# Output_Schematic.net
KiCad netlist of a schematic drawn in Altium Designer
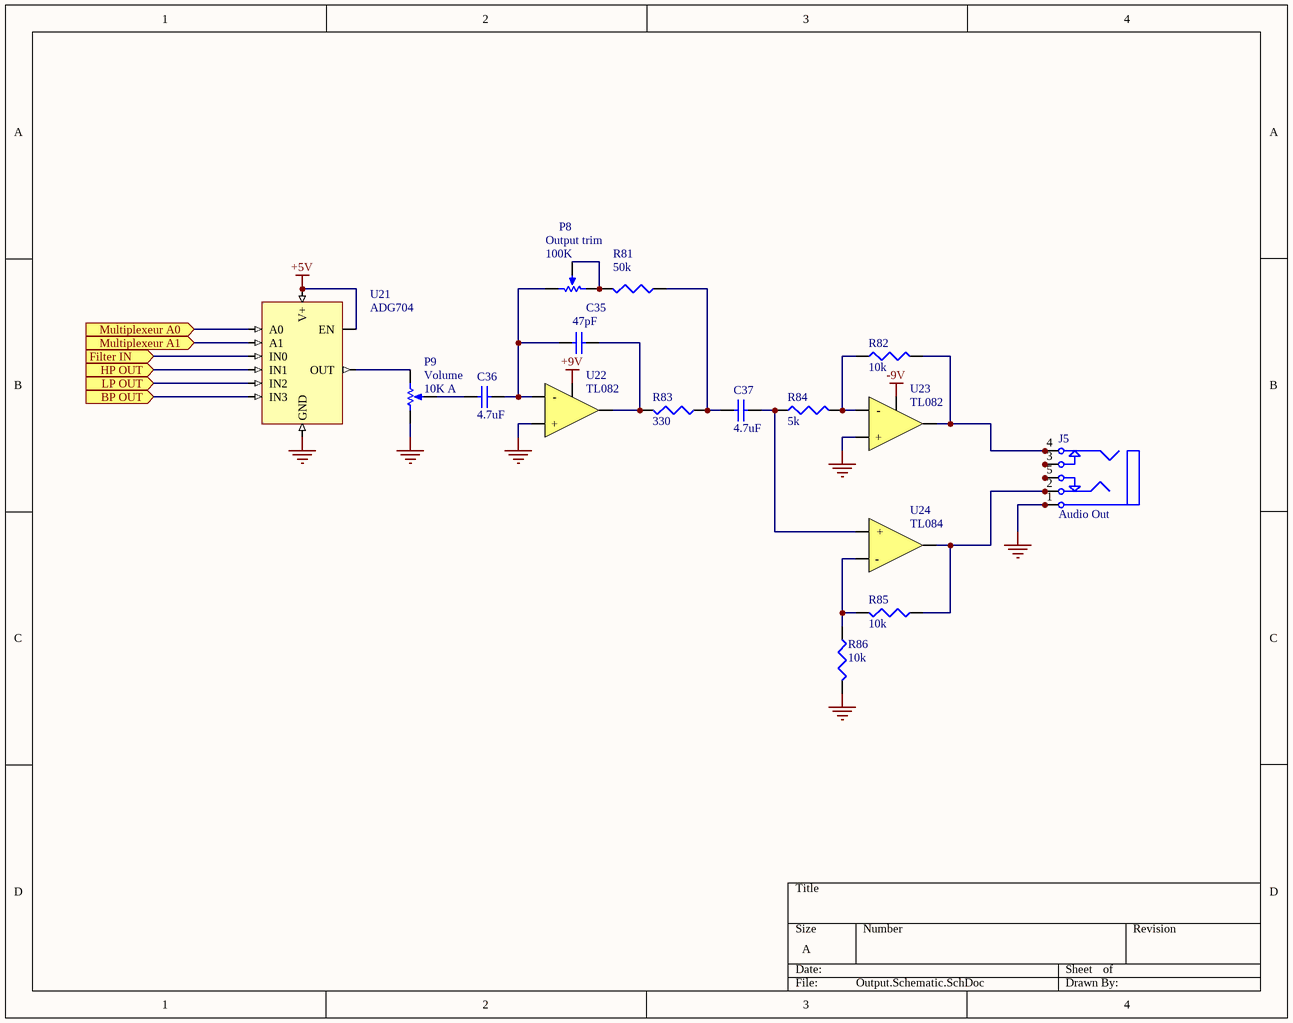
[diagram p0: Output.Schematic.SchDoc]

(export (version "E")
  (design (tool "Eeschema 10.0.6"))
  (components
    (comp (ref "C35")
      (value "47pF")
      (footprint "CAPC1608N")
      (description "Capacitor (Semiconductor SIM Model)")
      (fields (field (name "PUBLISHER") "Altium Limited"))
      (libsource (lib "Miscellaneous Devices") (part "Cap Semi"))
    )
    (comp (ref "C36")
      (value "4.7uF")
      (footprint "CAPC1608N")
      (description "Capacitor (Semiconductor SIM Model)")
      (fields (field (name "PUBLISHER") "Altium Limited"))
      (libsource (lib "Miscellaneous Devices") (part "Cap Semi"))
    )
    (comp (ref "C37")
      (value "4.7uF")
      (footprint "CAPC1608N")
      (description "Capacitor (Semiconductor SIM Model)")
      (fields (field (name "PUBLISHER") "Altium Limited"))
      (libsource (lib "Miscellaneous Devices") (part "Cap Semi"))
    )
    (comp (ref "J5")
      (value "Audio Out")
      (footprint "ST-3150-5N")
      (description "3-Conductor Jack with 2 break contacts (normals) and 2 auxiliary make contacts")
      (fields (field (name "PUBLISHER") "Altium Limited"))
      (libsource (lib "Miscellaneous Connectors") (part "Phonejack Stereo SW"))
    )
    (comp (ref "P8")
      (value "Output trim")
      (footprint "BOURNS Trim pot")
      (description "Potentiometer")
      (fields (field (name "ALTIUM_VALUE") "100K") (field (name "PUBLISHER") "Altium Limited"))
      (libsource (lib "Miscellaneous Devices") (part "RPot"))
    )
    (comp (ref "P9")
      (value "Volume")
      (footprint "ALPS Potentiometer")
      (description "Potentiometer")
      (fields (field (name "ALTIUM_VALUE") "10K A") (field (name "PUBLISHER") "Altium Limited"))
      (libsource (lib "Miscellaneous Devices") (part "RPot"))
    )
    (comp (ref "R81")
      (value "50k")
      (footprint "CAPC1608N")
      (description "Resistor")
      (fields (field (name "PUBLISHER") "Altium Limited"))
      (libsource (lib "Miscellaneous Devices") (part "Res3"))
    )
    (comp (ref "R82")
      (value "10k")
      (footprint "CAPC1608N")
      (description "Resistor")
      (fields (field (name "PUBLISHER") "Altium Limited"))
      (libsource (lib "Miscellaneous Devices") (part "Res3"))
    )
    (comp (ref "R83")
      (value "330")
      (footprint "CAPC1608N")
      (description "Resistor")
      (fields (field (name "PUBLISHER") "Altium Limited"))
      (libsource (lib "Miscellaneous Devices") (part "Res3"))
    )
    (comp (ref "R84")
      (value "5k")
      (footprint "CAPC1608N")
      (description "Resistor")
      (fields (field (name "PUBLISHER") "Altium Limited"))
      (libsource (lib "Miscellaneous Devices") (part "Res3"))
    )
    (comp (ref "R85")
      (value "10k")
      (footprint "J1-0603")
      (description "Resistor")
      (fields (field (name "PUBLISHER") "Altium Limited"))
      (libsource (lib "Miscellaneous Devices") (part "Res3"))
    )
    (comp (ref "R86")
      (value "10k")
      (footprint "RESC6332")
      (description "Resistor")
      (fields (field (name "PUBLISHER") "Altium Limited"))
      (libsource (lib "Miscellaneous Devices") (part "Res3"))
    )
    (comp (ref "U21")
      (value "ADG704")
      (footprint "ADG704")
      (libsource (lib "SynthyTwo.Components") (part "ADG704"))
    )
    (comp (ref "U22")
      (value "TL082")
      (footprint "TL084_3PADS+ALIM")
      (libsource (lib "SynthyTwo.Components") (part "TL082"))
    )
    (comp (ref "U23")
      (value "TL082")
      (footprint "TL084_3PADS+ALIM")
      (libsource (lib "SynthyTwo.Components") (part "TL082"))
    )
    (comp (ref "U24")
      (value "TL084")
      (footprint "TL084_3PADS")
      (libsource (lib "SynthyTwo.Components") (part "TL084"))
    )
  )
  (nets
    (net (code "1") (name "+5V") (class "Default")
      (node (ref "U21") (pin "5") (pinfunction "EN_5") (pintype "passive"))
      (node (ref "U21") (pin "6") (pinfunction "V+_6") (pintype "input"))
    )
    (net (code "2") (name "+9V") (class "Default")
      (node (ref "U22") (pin "4") (pinfunction "VCC+_4") (pintype "passive"))
    )
    (net (code "3") (name "-9V") (class "Default")
      (node (ref "U23") (pin "4") (pinfunction "VCC+_4") (pintype "passive"))
    )
    (net (code "4") (name "/BP OUT") (class "Default")
      (node (ref "U21") (pin "7") (pinfunction "IN3_7") (pintype "input"))
    )
    (net (code "5") (name "/Filter IN") (class "Default")
      (node (ref "U21") (pin "2") (pinfunction "IN0_2") (pintype "input"))
    )
    (net (code "6") (name "/HP OUT") (class "Default")
      (node (ref "U21") (pin "9") (pinfunction "IN1_9") (pintype "input"))
    )
    (net (code "7") (name "/LP OUT") (class "Default")
      (node (ref "U21") (pin "4") (pinfunction "IN2_4") (pintype "input"))
    )
    (net (code "8") (name "/Multiplexeur A0") (class "Default")
      (node (ref "U21") (pin "1") (pinfunction "A0_1") (pintype "input"))
    )
    (net (code "9") (name "/Multiplexeur A1") (class "Default")
      (node (ref "U21") (pin "10") (pinfunction "A1_10") (pintype "input"))
    )
    (net (code "10") (name "GND") (class "Default")
      (node (ref "J5") (pin "1") (pinfunction "1_1") (pintype "passive"))
      (node (ref "J5") (pin "1A") (pinfunction "1A_1A") (pintype "passive"))
      (node (ref "J5") (pin "1B") (pinfunction "1B_1B") (pintype "passive"))
      (node (ref "P9") (pin "1") (pinfunction "TOP_1") (pintype "passive"))
      (node (ref "R86") (pin "2") (pinfunction "2_2") (pintype "passive"))
      (node (ref "U21") (pin "3") (pinfunction "GND_3") (pintype "input"))
      (node (ref "U22") (pin "3") (pinfunction "+_3") (pintype "passive"))
      (node (ref "U23") (pin "3") (pinfunction "+_3") (pintype "passive"))
    )
    (net (code "11") (name "Net-(C37-Pad1)") (class "Default")
      (node (ref "C37") (pin "1") (pinfunction "1_1") (pintype "passive"))
      (node (ref "R81") (pin "1") (pinfunction "1_1") (pintype "passive"))
      (node (ref "R83") (pin "1") (pinfunction "1_1") (pintype "passive"))
    )
    (net (code "12") (name "Net-(J5-Pad3)") (class "Default")
      (node (ref "J5") (pin "3") (pinfunction "3_3") (pintype "passive"))
      (node (ref "J5") (pin "3A") (pinfunction "3A_3A") (pintype "passive"))
      (node (ref "J5") (pin "3B") (pinfunction "3B_3B") (pintype "passive"))
    )
    (net (code "13") (name "Net-(J5-Pad5)") (class "Default")
      (node (ref "J5") (pin "5") (pinfunction "5_5") (pintype "passive"))
      (node (ref "J5") (pin "5A") (pinfunction "5A_5A") (pintype "passive"))
      (node (ref "J5") (pin "5B") (pinfunction "5B_5B") (pintype "passive"))
    )
    (net (code "14") (name "Net-(P8-BOT)") (class "Default")
      (node (ref "P8") (pin "2") (pinfunction "BOT_2") (pintype "passive"))
      (node (ref "P8") (pin "3") (pinfunction "TAP_3") (pintype "passive"))
      (node (ref "R81") (pin "2") (pinfunction "2_2") (pintype "passive"))
    )
    (net (code "15") (name "Net-(P8-TOP)") (class "Default")
      (node (ref "C35") (pin "1") (pinfunction "1_1") (pintype "passive"))
      (node (ref "C36") (pin "2") (pinfunction "2_2") (pintype "passive"))
      (node (ref "P8") (pin "1") (pinfunction "TOP_1") (pintype "passive"))
      (node (ref "U22") (pin "2") (pinfunction "-_2") (pintype "passive"))
    )
    (net (code "16") (name "Net-(P9-BOT)") (class "Default")
      (node (ref "P9") (pin "2") (pinfunction "BOT_2") (pintype "passive"))
      (node (ref "U21") (pin "8") (pinfunction "OUT_8") (pintype "output"))
    )
    (net (code "17") (name "Net-(P9-TAP)") (class "Default")
      (node (ref "C36") (pin "1") (pinfunction "1_1") (pintype "passive"))
      (node (ref "P9") (pin "3") (pinfunction "TAP_3") (pintype "passive"))
    )
    (net (code "18") (name "Net-(U22-OUT)") (class "Default")
      (node (ref "C35") (pin "2") (pinfunction "2_2") (pintype "passive"))
      (node (ref "R83") (pin "2") (pinfunction "2_2") (pintype "passive"))
      (node (ref "U22") (pin "1") (pinfunction "OUT_1") (pintype "passive"))
    )
    (net (code "19") (name "Net-(U23--)") (class "Default")
      (node (ref "R82") (pin "1") (pinfunction "1_1") (pintype "passive"))
      (node (ref "R84") (pin "2") (pinfunction "2_2") (pintype "passive"))
      (node (ref "U23") (pin "2") (pinfunction "-_2") (pintype "passive"))
    )
    (net (code "20") (name "Net-(U23-OUT)") (class "Default")
      (node (ref "J5") (pin "4") (pinfunction "4_4") (pintype "passive"))
      (node (ref "J5") (pin "4A") (pinfunction "4A_4A") (pintype "passive"))
      (node (ref "J5") (pin "4B") (pinfunction "4B_4B") (pintype "passive"))
      (node (ref "R82") (pin "2") (pinfunction "2_2") (pintype "passive"))
      (node (ref "U23") (pin "1") (pinfunction "OUT_1") (pintype "passive"))
    )
    (net (code "21") (name "Net-(U24-+)") (class "Default")
      (node (ref "C37") (pin "2") (pinfunction "2_2") (pintype "passive"))
      (node (ref "R84") (pin "1") (pinfunction "1_1") (pintype "passive"))
      (node (ref "U24") (pin "3") (pinfunction "+_3") (pintype "passive"))
    )
    (net (code "22") (name "Net-(U24--)") (class "Default")
      (node (ref "R85") (pin "2") (pinfunction "2_2") (pintype "passive"))
      (node (ref "R86") (pin "1") (pinfunction "1_1") (pintype "passive"))
      (node (ref "U24") (pin "2") (pinfunction "-_2") (pintype "passive"))
    )
    (net (code "23") (name "Net-(U24-OUT)") (class "Default")
      (node (ref "J5") (pin "2") (pinfunction "2_2") (pintype "passive"))
      (node (ref "J5") (pin "2A") (pinfunction "2A_2A") (pintype "passive"))
      (node (ref "J5") (pin "2B") (pinfunction "2B_2B") (pintype "passive"))
      (node (ref "R85") (pin "1") (pinfunction "1_1") (pintype "passive"))
      (node (ref "U24") (pin "1") (pinfunction "OUT_1") (pintype "passive"))
    )
  )
)
